# MultifyMainDriver.net
KiCad netlist of a schematic drawn in EAGLE
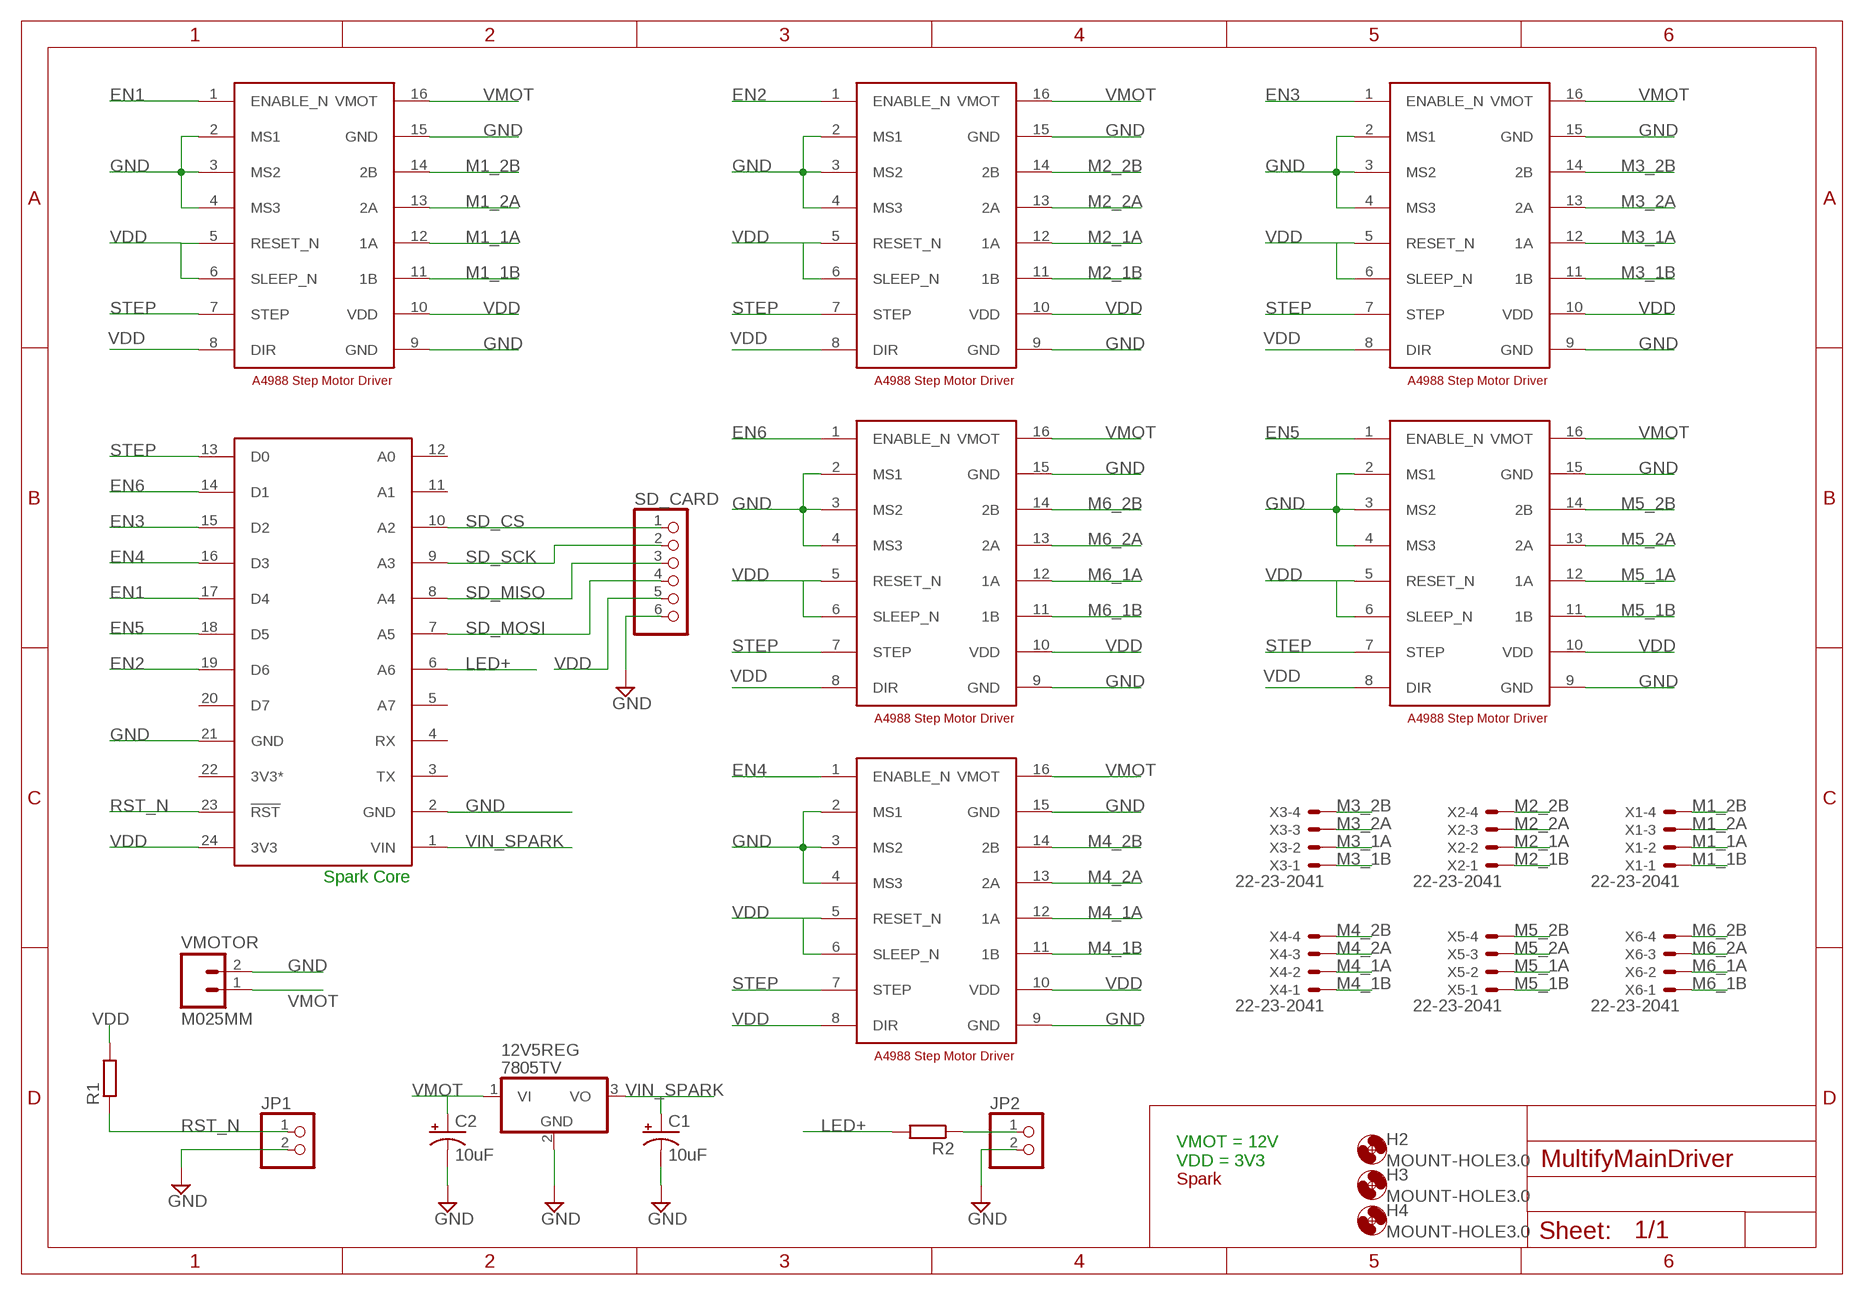
[diagram p0: schematic, sheet 1]

(export (version "E")
  (design (tool "Eeschema 10.0.6"))
  (components
    (comp (ref "12V5REG")
      (value "7805TV")
      (footprint "eagle-import:TO220V")
      (libsource (lib "eagle-import") (part "78TV05"))
    )
    (comp (ref "C1")
      (value "10uF")
      (footprint "eagle-import:E3,5-8")
      (libsource (lib "eagle-import") (part "CPOL-USE3.5-8"))
    )
    (comp (ref "C2")
      (value "10uF")
      (footprint "eagle-import:E3,5-8")
      (libsource (lib "eagle-import") (part "CPOL-USE3.5-8"))
    )
    (comp (ref "DRIVER1")
      (value "A4988_DEV")
      (footprint "eagle-import:A4988_PAC")
      (libsource (lib "eagle-import") (part "A4988_DEV"))
    )
    (comp (ref "DRIVER2")
      (value "A4988_DEV")
      (footprint "eagle-import:A4988_PAC")
      (libsource (lib "eagle-import") (part "A4988_DEV"))
    )
    (comp (ref "DRIVER3")
      (value "A4988_DEV")
      (footprint "eagle-import:A4988_PAC")
      (libsource (lib "eagle-import") (part "A4988_DEV"))
    )
    (comp (ref "DRIVER4")
      (value "A4988_DEV")
      (footprint "eagle-import:A4988_PAC")
      (libsource (lib "eagle-import") (part "A4988_DEV"))
    )
    (comp (ref "DRIVER5")
      (value "A4988_DEV")
      (footprint "eagle-import:A4988_PAC")
      (libsource (lib "eagle-import") (part "A4988_DEV"))
    )
    (comp (ref "DRIVER6")
      (value "A4988_DEV")
      (footprint "eagle-import:A4988_PAC")
      (libsource (lib "eagle-import") (part "A4988_DEV"))
    )
    (comp (ref "H2")
      (value "MOUNT-HOLE3.0")
      (footprint "eagle-import:3,0")
      (libsource (lib "eagle-import") (part "MOUNT-HOLE3.0"))
    )
    (comp (ref "H3")
      (value "MOUNT-HOLE3.0")
      (footprint "eagle-import:3,0")
      (libsource (lib "eagle-import") (part "MOUNT-HOLE3.0"))
    )
    (comp (ref "H4")
      (value "MOUNT-HOLE3.0")
      (footprint "eagle-import:3,0")
      (libsource (lib "eagle-import") (part "MOUNT-HOLE3.0"))
    )
    (comp (ref "JP1")
      (value "PINHD-1X2")
      (footprint "eagle-import:1X02")
      (libsource (lib "eagle-import") (part "PINHD-1X2"))
    )
    (comp (ref "JP2")
      (value "PINHD-1X2")
      (footprint "eagle-import:1X02")
      (libsource (lib "eagle-import") (part "PINHD-1X2"))
    )
    (comp (ref "R1")
      (value "R-EU_0207/7")
      (footprint "eagle-import:0207_7")
      (libsource (lib "eagle-import") (part "R-EU_0207/7"))
    )
    (comp (ref "R2")
      (value "R-EU_0207/7")
      (footprint "eagle-import:0207_7")
      (libsource (lib "eagle-import") (part "R-EU_0207/7"))
    )
    (comp (ref "SD_CARD")
      (value "PINHD-1X6")
      (footprint "eagle-import:1X06")
      (libsource (lib "eagle-import") (part "PINHD-1X6"))
    )
    (comp (ref "SPARK")
      (value "SPARK_CORECORE")
      (footprint "eagle-import:SPARK_CORE")
      (libsource (lib "eagle-import") (part "SPARK_CORECORE"))
    )
    (comp (ref "U$2")
      (value "SPARK_LOGO_WITH_PLANE")
      (footprint "eagle-import:SPARK_LOGO_PLUS_PLANE")
      (libsource (lib "eagle-import") (part "SPARK_LOGO_WITH_PLANE"))
    )
    (comp (ref "VMOTOR")
      (value "M025MM")
      (footprint "eagle-import:SCREWTERMINAL-5MM-2")
      (libsource (lib "eagle-import") (part "M025MM"))
    )
    (comp (ref "X1")
      (value "22-23-2041")
      (footprint "eagle-import:22-23-2041")
      (fields (field (name "MF") "MOLEX"))
      (libsource (lib "eagle-import") (part "22-23-2041"))
    )
    (comp (ref "X2")
      (value "22-23-2041")
      (footprint "eagle-import:22-23-2041")
      (fields (field (name "MF") "MOLEX"))
      (libsource (lib "eagle-import") (part "22-23-2041"))
    )
    (comp (ref "X3")
      (value "22-23-2041")
      (footprint "eagle-import:22-23-2041")
      (fields (field (name "MF") "MOLEX"))
      (libsource (lib "eagle-import") (part "22-23-2041"))
    )
    (comp (ref "X4")
      (value "22-23-2041")
      (footprint "eagle-import:22-23-2041")
      (fields (field (name "MF") "MOLEX"))
      (libsource (lib "eagle-import") (part "22-23-2041"))
    )
    (comp (ref "X5")
      (value "22-23-2041")
      (footprint "eagle-import:22-23-2041")
      (fields (field (name "MF") "MOLEX"))
      (libsource (lib "eagle-import") (part "22-23-2041"))
    )
    (comp (ref "X6")
      (value "22-23-2041")
      (footprint "eagle-import:22-23-2041")
      (fields (field (name "MF") "MOLEX"))
      (libsource (lib "eagle-import") (part "22-23-2041"))
    )
  )
  (nets
    (net (code "1") (name "/3V3*") (class "Default")
      (node (ref "SPARK") (pin "22") (pinfunction "3V3*_22") (pintype "power_in"))
    )
    (net (code "2") (name "/EN1") (class "Default")
      (node (ref "DRIVER1") (pin "1") (pinfunction "ENABLE_N_1") (pintype "bidirectional"))
      (node (ref "SPARK") (pin "17") (pinfunction "D4_17") (pintype "bidirectional"))
    )
    (net (code "3") (name "/EN2") (class "Default")
      (node (ref "DRIVER2") (pin "1") (pinfunction "ENABLE_N_1") (pintype "bidirectional"))
      (node (ref "SPARK") (pin "19") (pinfunction "D6_19") (pintype "bidirectional"))
    )
    (net (code "4") (name "/EN3") (class "Default")
      (node (ref "DRIVER3") (pin "1") (pinfunction "ENABLE_N_1") (pintype "bidirectional"))
      (node (ref "SPARK") (pin "15") (pinfunction "D2_15") (pintype "bidirectional"))
    )
    (net (code "5") (name "/EN4") (class "Default")
      (node (ref "DRIVER4") (pin "1") (pinfunction "ENABLE_N_1") (pintype "bidirectional"))
      (node (ref "SPARK") (pin "16") (pinfunction "D3_16") (pintype "bidirectional"))
    )
    (net (code "6") (name "/EN5") (class "Default")
      (node (ref "DRIVER6") (pin "1") (pinfunction "ENABLE_N_1") (pintype "bidirectional"))
      (node (ref "SPARK") (pin "18") (pinfunction "D5_18") (pintype "bidirectional"))
    )
    (net (code "7") (name "/EN6") (class "Default")
      (node (ref "DRIVER5") (pin "1") (pinfunction "ENABLE_N_1") (pintype "bidirectional"))
      (node (ref "SPARK") (pin "14") (pinfunction "D1_14") (pintype "bidirectional"))
    )
    (net (code "8") (name "/LED+") (class "Default")
      (node (ref "R2") (pin "2") (pinfunction "2_2") (pintype "passive"))
      (node (ref "SPARK") (pin "6") (pinfunction "A6_6") (pintype "bidirectional"))
    )
    (net (code "9") (name "/M1_1A") (class "Default")
      (node (ref "DRIVER1") (pin "12") (pinfunction "1A_12") (pintype "bidirectional"))
      (node (ref "X1") (pin "2") (pinfunction "S_2") (pintype "passive"))
    )
    (net (code "10") (name "/M1_1B") (class "Default")
      (node (ref "DRIVER1") (pin "11") (pinfunction "1B_11") (pintype "bidirectional"))
      (node (ref "X1") (pin "1") (pinfunction "S_1") (pintype "passive"))
    )
    (net (code "11") (name "/M1_2A") (class "Default")
      (node (ref "DRIVER1") (pin "13") (pinfunction "2A_13") (pintype "bidirectional"))
      (node (ref "X1") (pin "3") (pinfunction "S_3") (pintype "passive"))
    )
    (net (code "12") (name "/M1_2B") (class "Default")
      (node (ref "DRIVER1") (pin "14") (pinfunction "2B_14") (pintype "bidirectional"))
      (node (ref "X1") (pin "4") (pinfunction "S_4") (pintype "passive"))
    )
    (net (code "13") (name "/M2_1A") (class "Default")
      (node (ref "DRIVER2") (pin "12") (pinfunction "1A_12") (pintype "bidirectional"))
      (node (ref "X2") (pin "2") (pinfunction "S_2") (pintype "passive"))
    )
    (net (code "14") (name "/M2_1B") (class "Default")
      (node (ref "DRIVER2") (pin "11") (pinfunction "1B_11") (pintype "bidirectional"))
      (node (ref "X2") (pin "1") (pinfunction "S_1") (pintype "passive"))
    )
    (net (code "15") (name "/M2_2A") (class "Default")
      (node (ref "DRIVER2") (pin "13") (pinfunction "2A_13") (pintype "bidirectional"))
      (node (ref "X2") (pin "3") (pinfunction "S_3") (pintype "passive"))
    )
    (net (code "16") (name "/M2_2B") (class "Default")
      (node (ref "DRIVER2") (pin "14") (pinfunction "2B_14") (pintype "bidirectional"))
      (node (ref "X2") (pin "4") (pinfunction "S_4") (pintype "passive"))
    )
    (net (code "17") (name "/M3_1A") (class "Default")
      (node (ref "DRIVER3") (pin "12") (pinfunction "1A_12") (pintype "bidirectional"))
      (node (ref "X3") (pin "2") (pinfunction "S_2") (pintype "passive"))
    )
    (net (code "18") (name "/M3_1B") (class "Default")
      (node (ref "DRIVER3") (pin "11") (pinfunction "1B_11") (pintype "bidirectional"))
      (node (ref "X3") (pin "1") (pinfunction "S_1") (pintype "passive"))
    )
    (net (code "19") (name "/M3_2A") (class "Default")
      (node (ref "DRIVER3") (pin "13") (pinfunction "2A_13") (pintype "bidirectional"))
      (node (ref "X3") (pin "3") (pinfunction "S_3") (pintype "passive"))
    )
    (net (code "20") (name "/M3_2B") (class "Default")
      (node (ref "DRIVER3") (pin "14") (pinfunction "2B_14") (pintype "bidirectional"))
      (node (ref "X3") (pin "4") (pinfunction "S_4") (pintype "passive"))
    )
    (net (code "21") (name "/M4_1A") (class "Default")
      (node (ref "DRIVER4") (pin "12") (pinfunction "1A_12") (pintype "bidirectional"))
      (node (ref "X4") (pin "2") (pinfunction "S_2") (pintype "passive"))
    )
    (net (code "22") (name "/M4_1B") (class "Default")
      (node (ref "DRIVER4") (pin "11") (pinfunction "1B_11") (pintype "bidirectional"))
      (node (ref "X4") (pin "1") (pinfunction "S_1") (pintype "passive"))
    )
    (net (code "23") (name "/M4_2A") (class "Default")
      (node (ref "DRIVER4") (pin "13") (pinfunction "2A_13") (pintype "bidirectional"))
      (node (ref "X4") (pin "3") (pinfunction "S_3") (pintype "passive"))
    )
    (net (code "24") (name "/M4_2B") (class "Default")
      (node (ref "DRIVER4") (pin "14") (pinfunction "2B_14") (pintype "bidirectional"))
      (node (ref "X4") (pin "4") (pinfunction "S_4") (pintype "passive"))
    )
    (net (code "25") (name "/M5_1A") (class "Default")
      (node (ref "DRIVER6") (pin "12") (pinfunction "1A_12") (pintype "bidirectional"))
      (node (ref "X5") (pin "2") (pinfunction "S_2") (pintype "passive"))
    )
    (net (code "26") (name "/M5_1B") (class "Default")
      (node (ref "DRIVER6") (pin "11") (pinfunction "1B_11") (pintype "bidirectional"))
      (node (ref "X5") (pin "1") (pinfunction "S_1") (pintype "passive"))
    )
    (net (code "27") (name "/M5_2A") (class "Default")
      (node (ref "DRIVER6") (pin "13") (pinfunction "2A_13") (pintype "bidirectional"))
      (node (ref "X5") (pin "3") (pinfunction "S_3") (pintype "passive"))
    )
    (net (code "28") (name "/M5_2B") (class "Default")
      (node (ref "DRIVER6") (pin "14") (pinfunction "2B_14") (pintype "bidirectional"))
      (node (ref "X5") (pin "4") (pinfunction "S_4") (pintype "passive"))
    )
    (net (code "29") (name "/M6_1A") (class "Default")
      (node (ref "DRIVER5") (pin "12") (pinfunction "1A_12") (pintype "bidirectional"))
      (node (ref "X6") (pin "2") (pinfunction "S_2") (pintype "passive"))
    )
    (net (code "30") (name "/M6_1B") (class "Default")
      (node (ref "DRIVER5") (pin "11") (pinfunction "1B_11") (pintype "bidirectional"))
      (node (ref "X6") (pin "1") (pinfunction "S_1") (pintype "passive"))
    )
    (net (code "31") (name "/M6_2A") (class "Default")
      (node (ref "DRIVER5") (pin "13") (pinfunction "2A_13") (pintype "bidirectional"))
      (node (ref "X6") (pin "3") (pinfunction "S_3") (pintype "passive"))
    )
    (net (code "32") (name "/M6_2B") (class "Default")
      (node (ref "DRIVER5") (pin "14") (pinfunction "2B_14") (pintype "bidirectional"))
      (node (ref "X6") (pin "4") (pinfunction "S_4") (pintype "passive"))
    )
    (net (code "33") (name "/RST_N") (class "Default")
      (node (ref "JP1") (pin "1") (pinfunction "1_1") (pintype "passive"))
      (node (ref "R1") (pin "1") (pinfunction "1_1") (pintype "passive"))
      (node (ref "SPARK") (pin "23") (pinfunction "~{RST}_23") (pintype "bidirectional"))
    )
    (net (code "34") (name "/SD_CS") (class "Default")
      (node (ref "SD_CARD") (pin "1") (pinfunction "1_1") (pintype "passive"))
      (node (ref "SPARK") (pin "10") (pinfunction "A2_10") (pintype "bidirectional"))
    )
    (net (code "35") (name "/SD_MISO") (class "Default")
      (node (ref "SD_CARD") (pin "3") (pinfunction "3_3") (pintype "passive"))
      (node (ref "SPARK") (pin "8") (pinfunction "A4_8") (pintype "bidirectional"))
    )
    (net (code "36") (name "/SD_MOSI") (class "Default")
      (node (ref "SD_CARD") (pin "4") (pinfunction "4_4") (pintype "passive"))
      (node (ref "SPARK") (pin "7") (pinfunction "A5_7") (pintype "bidirectional"))
    )
    (net (code "37") (name "/SD_SCK") (class "Default")
      (node (ref "SD_CARD") (pin "2") (pinfunction "2_2") (pintype "passive"))
      (node (ref "SPARK") (pin "9") (pinfunction "A3_9") (pintype "bidirectional"))
    )
    (net (code "38") (name "/STEP") (class "Default")
      (node (ref "DRIVER1") (pin "7") (pinfunction "STEP_7") (pintype "bidirectional"))
      (node (ref "DRIVER2") (pin "7") (pinfunction "STEP_7") (pintype "bidirectional"))
      (node (ref "DRIVER3") (pin "7") (pinfunction "STEP_7") (pintype "bidirectional"))
      (node (ref "DRIVER4") (pin "7") (pinfunction "STEP_7") (pintype "bidirectional"))
      (node (ref "DRIVER5") (pin "7") (pinfunction "STEP_7") (pintype "bidirectional"))
      (node (ref "DRIVER6") (pin "7") (pinfunction "STEP_7") (pintype "bidirectional"))
      (node (ref "SPARK") (pin "13") (pinfunction "D0_13") (pintype "bidirectional"))
    )
    (net (code "39") (name "/VDD") (class "Default")
      (node (ref "DRIVER1") (pin "10") (pinfunction "VDD_10") (pintype "bidirectional"))
      (node (ref "DRIVER1") (pin "5") (pinfunction "RESET_N_5") (pintype "bidirectional"))
      (node (ref "DRIVER1") (pin "6") (pinfunction "SLEEP_N_6") (pintype "bidirectional"))
      (node (ref "DRIVER1") (pin "8") (pinfunction "DIR_8") (pintype "bidirectional"))
      (node (ref "DRIVER2") (pin "10") (pinfunction "VDD_10") (pintype "bidirectional"))
      (node (ref "DRIVER2") (pin "5") (pinfunction "RESET_N_5") (pintype "bidirectional"))
      (node (ref "DRIVER2") (pin "6") (pinfunction "SLEEP_N_6") (pintype "bidirectional"))
      (node (ref "DRIVER2") (pin "8") (pinfunction "DIR_8") (pintype "bidirectional"))
      (node (ref "DRIVER3") (pin "10") (pinfunction "VDD_10") (pintype "bidirectional"))
      (node (ref "DRIVER3") (pin "5") (pinfunction "RESET_N_5") (pintype "bidirectional"))
      (node (ref "DRIVER3") (pin "6") (pinfunction "SLEEP_N_6") (pintype "bidirectional"))
      (node (ref "DRIVER3") (pin "8") (pinfunction "DIR_8") (pintype "bidirectional"))
      (node (ref "DRIVER4") (pin "10") (pinfunction "VDD_10") (pintype "bidirectional"))
      (node (ref "DRIVER4") (pin "5") (pinfunction "RESET_N_5") (pintype "bidirectional"))
      (node (ref "DRIVER4") (pin "6") (pinfunction "SLEEP_N_6") (pintype "bidirectional"))
      (node (ref "DRIVER4") (pin "8") (pinfunction "DIR_8") (pintype "bidirectional"))
      (node (ref "DRIVER5") (pin "10") (pinfunction "VDD_10") (pintype "bidirectional"))
      (node (ref "DRIVER5") (pin "5") (pinfunction "RESET_N_5") (pintype "bidirectional"))
      (node (ref "DRIVER5") (pin "6") (pinfunction "SLEEP_N_6") (pintype "bidirectional"))
      (node (ref "DRIVER5") (pin "8") (pinfunction "DIR_8") (pintype "bidirectional"))
      (node (ref "DRIVER6") (pin "10") (pinfunction "VDD_10") (pintype "bidirectional"))
      (node (ref "DRIVER6") (pin "5") (pinfunction "RESET_N_5") (pintype "bidirectional"))
      (node (ref "DRIVER6") (pin "6") (pinfunction "SLEEP_N_6") (pintype "bidirectional"))
      (node (ref "DRIVER6") (pin "8") (pinfunction "DIR_8") (pintype "bidirectional"))
      (node (ref "R1") (pin "2") (pinfunction "2_2") (pintype "passive"))
      (node (ref "SD_CARD") (pin "5") (pinfunction "5_5") (pintype "passive"))
      (node (ref "SPARK") (pin "24") (pinfunction "3V3_24") (pintype "power_in"))
    )
    (net (code "40") (name "/VIN_SPARK") (class "Default")
      (node (ref "12V5REG") (pin "3") (pinfunction "VO_3") (pintype "passive"))
      (node (ref "C1") (pin "+") (pinfunction "+_+") (pintype "passive"))
      (node (ref "SPARK") (pin "1") (pinfunction "VIN_1") (pintype "power_in"))
    )
    (net (code "41") (name "/VMOT") (class "Default")
      (node (ref "12V5REG") (pin "1") (pinfunction "VI_1") (pintype "input"))
      (node (ref "C2") (pin "+") (pinfunction "+_+") (pintype "passive"))
      (node (ref "DRIVER1") (pin "16") (pinfunction "VMOT_16") (pintype "bidirectional"))
      (node (ref "DRIVER2") (pin "16") (pinfunction "VMOT_16") (pintype "bidirectional"))
      (node (ref "DRIVER3") (pin "16") (pinfunction "VMOT_16") (pintype "bidirectional"))
      (node (ref "DRIVER4") (pin "16") (pinfunction "VMOT_16") (pintype "bidirectional"))
      (node (ref "DRIVER5") (pin "16") (pinfunction "VMOT_16") (pintype "bidirectional"))
      (node (ref "DRIVER6") (pin "16") (pinfunction "VMOT_16") (pintype "bidirectional"))
      (node (ref "VMOTOR") (pin "1") (pinfunction "1_1") (pintype "passive"))
    )
    (net (code "42") (name "GND") (class "Default")
      (node (ref "12V5REG") (pin "2") (pinfunction "GND_2") (pintype "passive"))
      (node (ref "C1") (pin "-") (pinfunction "-_-") (pintype "passive"))
      (node (ref "C2") (pin "-") (pinfunction "-_-") (pintype "passive"))
      (node (ref "DRIVER1") (pin "15") (pinfunction "GND_15") (pintype "bidirectional"))
      (node (ref "DRIVER1") (pin "2") (pinfunction "MS1_2") (pintype "bidirectional"))
      (node (ref "DRIVER1") (pin "3") (pinfunction "MS2_3") (pintype "bidirectional"))
      (node (ref "DRIVER1") (pin "4") (pinfunction "MS3_4") (pintype "bidirectional"))
      (node (ref "DRIVER1") (pin "9") (pinfunction "GND_9") (pintype "bidirectional"))
      (node (ref "DRIVER2") (pin "15") (pinfunction "GND_15") (pintype "bidirectional"))
      (node (ref "DRIVER2") (pin "2") (pinfunction "MS1_2") (pintype "bidirectional"))
      (node (ref "DRIVER2") (pin "3") (pinfunction "MS2_3") (pintype "bidirectional"))
      (node (ref "DRIVER2") (pin "4") (pinfunction "MS3_4") (pintype "bidirectional"))
      (node (ref "DRIVER2") (pin "9") (pinfunction "GND_9") (pintype "bidirectional"))
      (node (ref "DRIVER3") (pin "15") (pinfunction "GND_15") (pintype "bidirectional"))
      (node (ref "DRIVER3") (pin "2") (pinfunction "MS1_2") (pintype "bidirectional"))
      (node (ref "DRIVER3") (pin "3") (pinfunction "MS2_3") (pintype "bidirectional"))
      (node (ref "DRIVER3") (pin "4") (pinfunction "MS3_4") (pintype "bidirectional"))
      (node (ref "DRIVER3") (pin "9") (pinfunction "GND_9") (pintype "bidirectional"))
      (node (ref "DRIVER4") (pin "15") (pinfunction "GND_15") (pintype "bidirectional"))
      (node (ref "DRIVER4") (pin "2") (pinfunction "MS1_2") (pintype "bidirectional"))
      (node (ref "DRIVER4") (pin "3") (pinfunction "MS2_3") (pintype "bidirectional"))
      (node (ref "DRIVER4") (pin "4") (pinfunction "MS3_4") (pintype "bidirectional"))
      (node (ref "DRIVER4") (pin "9") (pinfunction "GND_9") (pintype "bidirectional"))
      (node (ref "DRIVER5") (pin "15") (pinfunction "GND_15") (pintype "bidirectional"))
      (node (ref "DRIVER5") (pin "2") (pinfunction "MS1_2") (pintype "bidirectional"))
      (node (ref "DRIVER5") (pin "3") (pinfunction "MS2_3") (pintype "bidirectional"))
      (node (ref "DRIVER5") (pin "4") (pinfunction "MS3_4") (pintype "bidirectional"))
      (node (ref "DRIVER5") (pin "9") (pinfunction "GND_9") (pintype "bidirectional"))
      (node (ref "DRIVER6") (pin "15") (pinfunction "GND_15") (pintype "bidirectional"))
      (node (ref "DRIVER6") (pin "2") (pinfunction "MS1_2") (pintype "bidirectional"))
      (node (ref "DRIVER6") (pin "3") (pinfunction "MS2_3") (pintype "bidirectional"))
      (node (ref "DRIVER6") (pin "4") (pinfunction "MS3_4") (pintype "bidirectional"))
      (node (ref "DRIVER6") (pin "9") (pinfunction "GND_9") (pintype "bidirectional"))
      (node (ref "JP1") (pin "2") (pinfunction "2_2") (pintype "passive"))
      (node (ref "JP2") (pin "2") (pinfunction "2_2") (pintype "passive"))
      (node (ref "SD_CARD") (pin "6") (pinfunction "6_6") (pintype "passive"))
      (node (ref "SPARK") (pin "2") (pinfunction "GND_2") (pintype "power_in"))
      (node (ref "SPARK") (pin "21") (pinfunction "GND_21") (pintype "power_in"))
      (node (ref "VMOTOR") (pin "2") (pinfunction "2_2") (pintype "passive"))
    )
    (net (code "43") (name "Net-(JP2-Pad1)") (class "Default")
      (node (ref "JP2") (pin "1") (pinfunction "1_1") (pintype "passive"))
      (node (ref "R2") (pin "1") (pinfunction "1_1") (pintype "passive"))
    )
    (net (code "44") (name "unconnected-(SPARK-A0-Pad12)") (class "Default")
      (node (ref "SPARK") (pin "12") (pinfunction "A0_12") (pintype "bidirectional"))
    )
    (net (code "45") (name "unconnected-(SPARK-A1-Pad11)") (class "Default")
      (node (ref "SPARK") (pin "11") (pinfunction "A1_11") (pintype "bidirectional"))
    )
    (net (code "46") (name "unconnected-(SPARK-A7-Pad5)") (class "Default")
      (node (ref "SPARK") (pin "5") (pinfunction "A7_5") (pintype "bidirectional"))
    )
    (net (code "47") (name "unconnected-(SPARK-D7-Pad20)") (class "Default")
      (node (ref "SPARK") (pin "20") (pinfunction "D7_20") (pintype "bidirectional"))
    )
    (net (code "48") (name "unconnected-(SPARK-RX-Pad4)") (class "Default")
      (node (ref "SPARK") (pin "4") (pinfunction "RX_4") (pintype "bidirectional"))
    )
    (net (code "49") (name "unconnected-(SPARK-TX-Pad3)") (class "Default")
      (node (ref "SPARK") (pin "3") (pinfunction "TX_3") (pintype "bidirectional"))
    )
  )
)
